# EX-YU_16K_C64_CART.net
KiCad netlist of a schematic drawn in EAGLE
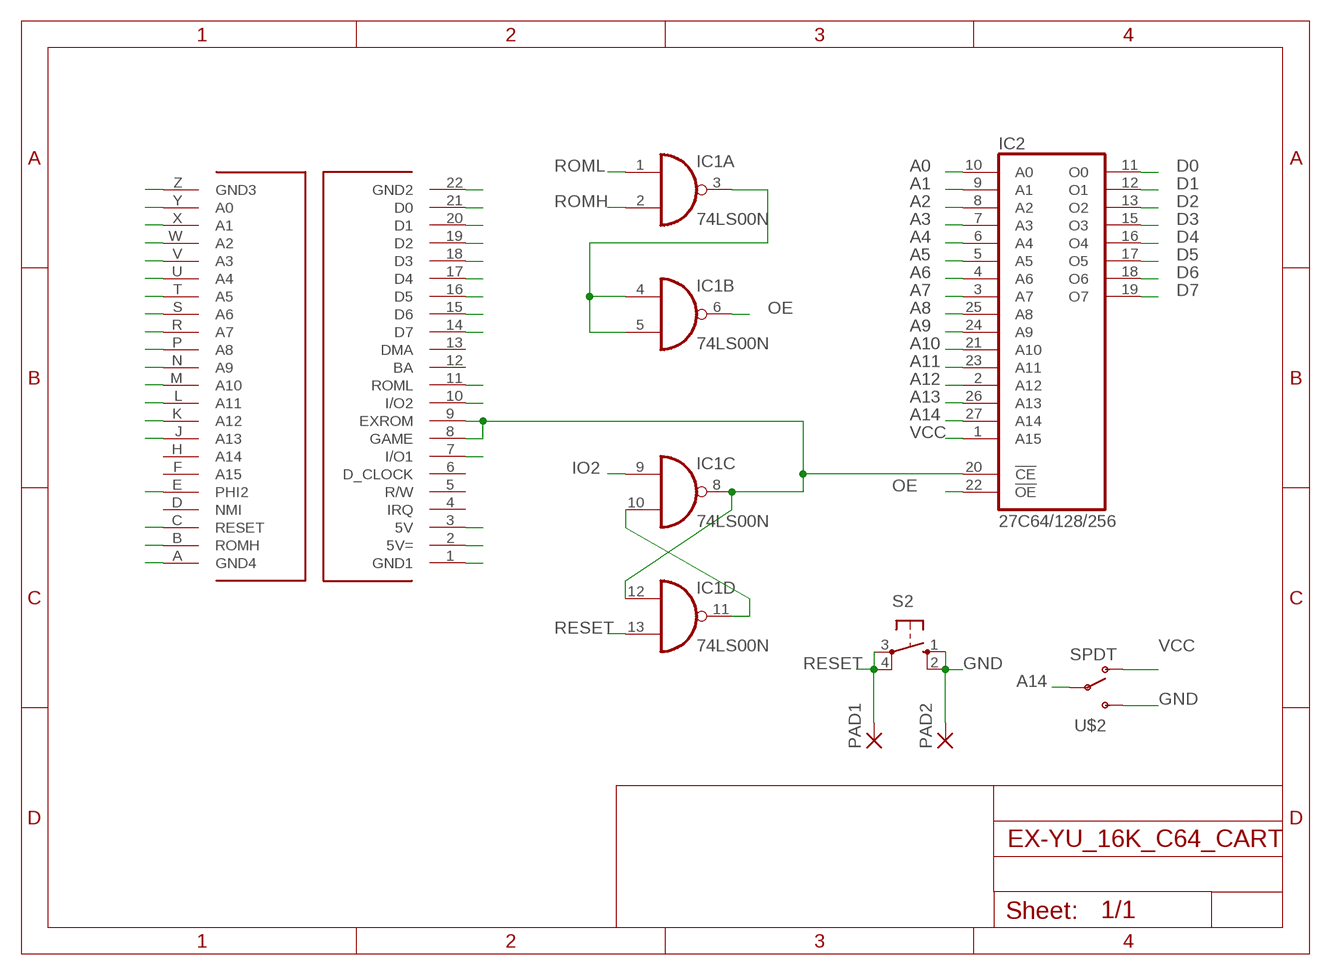
[diagram p0: schematic, sheet 1]

(export (version "E")
  (design (tool "Eeschema 10.0.6"))
  (components
    (comp (ref "IC1")
      (value "74LS00N")
      (footprint "eagle-import:DIL14")
      (libsource (lib "eagle-import") (part "7400NLS"))
    )
    (comp (ref "IC2")
      (value "27C64/128/256")
      (footprint "eagle-import:DIL28")
      (libsource (lib "eagle-import") (part "27512"))
    )
    (comp (ref "PAD1")
      (value "SMD5")
      (footprint "eagle-import:SMD2,54-5,08")
      (libsource (lib "eagle-import") (part "SMD5"))
    )
    (comp (ref "PAD2")
      (value "SMD5")
      (footprint "eagle-import:SMD2,54-5,08")
      (libsource (lib "eagle-import") (part "SMD5"))
    )
    (comp (ref "S2")
      (value "10-XX")
      (footprint "eagle-import:B3F-10XX")
      (fields (field (name "MPN") "B3F-1000"))
      (libsource (lib "eagle-import") (part "10-XX"))
    )
    (comp (ref "U$1")
      (value "C64_EXPANSION__CARTRIDGE")
      (footprint "eagle-import:C64_EXPANSION__CARTRIDGE")
      (libsource (lib "eagle-import") (part "C64_EXPANSION__CARTRIDGE"))
    )
    (comp (ref "U$2")
      (value "SPDT")
      (footprint "eagle-import:SPDT-SLIDE")
      (libsource (lib "eagle-import") (part "SPDT"))
    )
  )
  (nets
    (net (code "1") (name "/A0") (class "Default")
      (node (ref "IC2") (pin "10") (pinfunction "A0_10") (pintype "input"))
      (node (ref "U$1") (pin "Y") (pinfunction "A0_Y") (pintype "bidirectional"))
    )
    (net (code "2") (name "/A1") (class "Default")
      (node (ref "IC2") (pin "9") (pinfunction "A1_9") (pintype "input"))
      (node (ref "U$1") (pin "X") (pinfunction "A1_X") (pintype "bidirectional"))
    )
    (net (code "3") (name "/A2") (class "Default")
      (node (ref "IC2") (pin "8") (pinfunction "A2_8") (pintype "input"))
      (node (ref "U$1") (pin "W") (pinfunction "A2_W") (pintype "bidirectional"))
    )
    (net (code "4") (name "/A3") (class "Default")
      (node (ref "IC2") (pin "7") (pinfunction "A3_7") (pintype "input"))
      (node (ref "U$1") (pin "V") (pinfunction "A3_V") (pintype "bidirectional"))
    )
    (net (code "5") (name "/A4") (class "Default")
      (node (ref "IC2") (pin "6") (pinfunction "A4_6") (pintype "input"))
      (node (ref "U$1") (pin "U") (pinfunction "A4_U") (pintype "bidirectional"))
    )
    (net (code "6") (name "/A5") (class "Default")
      (node (ref "IC2") (pin "5") (pinfunction "A5_5") (pintype "input"))
      (node (ref "U$1") (pin "T") (pinfunction "A5_T") (pintype "bidirectional"))
    )
    (net (code "7") (name "/A6") (class "Default")
      (node (ref "IC2") (pin "4") (pinfunction "A6_4") (pintype "input"))
      (node (ref "U$1") (pin "S") (pinfunction "A6_S") (pintype "bidirectional"))
    )
    (net (code "8") (name "/A7") (class "Default")
      (node (ref "IC2") (pin "3") (pinfunction "A7_3") (pintype "input"))
      (node (ref "U$1") (pin "R") (pinfunction "A7_R") (pintype "bidirectional"))
    )
    (net (code "9") (name "/A8") (class "Default")
      (node (ref "IC2") (pin "25") (pinfunction "A8_25") (pintype "input"))
      (node (ref "U$1") (pin "P") (pinfunction "A8_P") (pintype "bidirectional"))
    )
    (net (code "10") (name "/A9") (class "Default")
      (node (ref "IC2") (pin "24") (pinfunction "A9_24") (pintype "input"))
      (node (ref "U$1") (pin "N") (pinfunction "A9_N") (pintype "bidirectional"))
    )
    (net (code "11") (name "/A10") (class "Default")
      (node (ref "IC2") (pin "21") (pinfunction "A10_21") (pintype "input"))
      (node (ref "U$1") (pin "M") (pinfunction "A10_M") (pintype "bidirectional"))
    )
    (net (code "12") (name "/A11") (class "Default")
      (node (ref "IC2") (pin "23") (pinfunction "A11_23") (pintype "input"))
      (node (ref "U$1") (pin "L") (pinfunction "A11_L") (pintype "bidirectional"))
    )
    (net (code "13") (name "/A12") (class "Default")
      (node (ref "IC2") (pin "2") (pinfunction "A12_2") (pintype "input"))
      (node (ref "U$1") (pin "K") (pinfunction "A12_K") (pintype "bidirectional"))
    )
    (net (code "14") (name "/A13") (class "Default")
      (node (ref "IC2") (pin "26") (pinfunction "A13_26") (pintype "input"))
      (node (ref "U$1") (pin "J") (pinfunction "A13_J") (pintype "bidirectional"))
    )
    (net (code "15") (name "/A14") (class "Default")
      (node (ref "IC2") (pin "27") (pinfunction "A14_27") (pintype "input"))
      (node (ref "U$2") (pin "2") (pinfunction "2_2") (pintype "passive"))
    )
    (net (code "16") (name "/D0") (class "Default")
      (node (ref "IC2") (pin "11") (pinfunction "O0_11") (pintype "tri_state"))
      (node (ref "U$1") (pin "21") (pinfunction "D0_21") (pintype "bidirectional"))
    )
    (net (code "17") (name "/D1") (class "Default")
      (node (ref "IC2") (pin "12") (pinfunction "O1_12") (pintype "tri_state"))
      (node (ref "U$1") (pin "20") (pinfunction "D1_20") (pintype "bidirectional"))
    )
    (net (code "18") (name "/D2") (class "Default")
      (node (ref "IC2") (pin "13") (pinfunction "O2_13") (pintype "tri_state"))
      (node (ref "U$1") (pin "19") (pinfunction "D2_19") (pintype "bidirectional"))
    )
    (net (code "19") (name "/D3") (class "Default")
      (node (ref "IC2") (pin "15") (pinfunction "O3_15") (pintype "tri_state"))
      (node (ref "U$1") (pin "18") (pinfunction "D3_18") (pintype "bidirectional"))
    )
    (net (code "20") (name "/D4") (class "Default")
      (node (ref "IC2") (pin "16") (pinfunction "O4_16") (pintype "tri_state"))
      (node (ref "U$1") (pin "17") (pinfunction "D4_17") (pintype "bidirectional"))
    )
    (net (code "21") (name "/D5") (class "Default")
      (node (ref "IC2") (pin "17") (pinfunction "O5_17") (pintype "tri_state"))
      (node (ref "U$1") (pin "16") (pinfunction "D5_16") (pintype "bidirectional"))
    )
    (net (code "22") (name "/D6") (class "Default")
      (node (ref "IC2") (pin "18") (pinfunction "O6_18") (pintype "tri_state"))
      (node (ref "U$1") (pin "15") (pinfunction "D6_15") (pintype "bidirectional"))
    )
    (net (code "23") (name "/D7") (class "Default")
      (node (ref "IC2") (pin "19") (pinfunction "O7_19") (pintype "tri_state"))
      (node (ref "U$1") (pin "14") (pinfunction "D7_14") (pintype "bidirectional"))
    )
    (net (code "24") (name "/GND") (class "Default")
      (node (ref "PAD2") (pin "1") (pinfunction "P_1") (pintype "passive"))
      (node (ref "S2") (pin "1") (pinfunction "S_1") (pintype "passive"))
      (node (ref "S2") (pin "2") (pinfunction "S1_2") (pintype "passive"))
      (node (ref "U$1") (pin "1") (pinfunction "GND1_1") (pintype "bidirectional"))
      (node (ref "U$1") (pin "22") (pinfunction "GND2_22") (pintype "bidirectional"))
      (node (ref "U$1") (pin "A") (pinfunction "GND4_A") (pintype "bidirectional"))
      (node (ref "U$1") (pin "Z") (pinfunction "GND3_Z") (pintype "bidirectional"))
      (node (ref "U$2") (pin "3") (pinfunction "3_3") (pintype "passive"))
    )
    (net (code "25") (name "/IO2") (class "Default")
      (node (ref "IC1") (pin "9") (pinfunction "I0_9") (pintype "input"))
      (node (ref "U$1") (pin "10") (pinfunction "I/O2_10") (pintype "bidirectional"))
    )
    (net (code "26") (name "/OE") (class "Default")
      (node (ref "IC1") (pin "6") (pinfunction "O_6") (pintype "output"))
      (node (ref "IC2") (pin "22") (pinfunction "~{OE}_22") (pintype "input"))
    )
    (net (code "27") (name "/RESET") (class "Default")
      (node (ref "IC1") (pin "13") (pinfunction "I1_13") (pintype "input"))
      (node (ref "PAD1") (pin "1") (pinfunction "P_1") (pintype "passive"))
      (node (ref "S2") (pin "3") (pinfunction "P_3") (pintype "passive"))
      (node (ref "S2") (pin "4") (pinfunction "P1_4") (pintype "passive"))
      (node (ref "U$1") (pin "C") (pinfunction "RESET_C") (pintype "bidirectional"))
    )
    (net (code "28") (name "/ROMH") (class "Default")
      (node (ref "IC1") (pin "2") (pinfunction "I1_2") (pintype "input"))
      (node (ref "U$1") (pin "B") (pinfunction "ROMH_B") (pintype "bidirectional"))
    )
    (net (code "29") (name "/ROML") (class "Default")
      (node (ref "IC1") (pin "1") (pinfunction "I0_1") (pintype "input"))
      (node (ref "U$1") (pin "11") (pinfunction "ROML_11") (pintype "bidirectional"))
    )
    (net (code "30") (name "/VCC") (class "Default")
      (node (ref "IC2") (pin "1") (pinfunction "A15_1") (pintype "input"))
      (node (ref "U$1") (pin "2") (pinfunction "5V=_2") (pintype "bidirectional"))
      (node (ref "U$1") (pin "3") (pinfunction "5V_3") (pintype "bidirectional"))
      (node (ref "U$2") (pin "1") (pinfunction "1_1") (pintype "passive"))
    )
    (net (code "31") (name "Net-(IC1A-O)") (class "Default")
      (node (ref "IC1") (pin "3") (pinfunction "O_3") (pintype "output"))
      (node (ref "IC1") (pin "4") (pinfunction "I0_4") (pintype "input"))
      (node (ref "IC1") (pin "5") (pinfunction "I1_5") (pintype "input"))
    )
    (net (code "32") (name "Net-(IC1C-I1)") (class "Default")
      (node (ref "IC1") (pin "10") (pinfunction "I1_10") (pintype "input"))
      (node (ref "IC1") (pin "11") (pinfunction "O_11") (pintype "output"))
    )
    (net (code "33") (name "Net-(IC1C-O)") (class "Default")
      (node (ref "IC1") (pin "12") (pinfunction "I0_12") (pintype "input"))
      (node (ref "IC1") (pin "8") (pinfunction "O_8") (pintype "output"))
      (node (ref "IC2") (pin "20") (pinfunction "~{CE}_20") (pintype "input"))
      (node (ref "U$1") (pin "8") (pinfunction "GAME_8") (pintype "bidirectional"))
      (node (ref "U$1") (pin "9") (pinfunction "EXROM_9") (pintype "bidirectional"))
    )
    (net (code "34") (name "unconnected-(U$1-A14-PadH)") (class "Default")
      (node (ref "U$1") (pin "H") (pinfunction "A14_H") (pintype "bidirectional"))
    )
    (net (code "35") (name "unconnected-(U$1-A15-PadF)") (class "Default")
      (node (ref "U$1") (pin "F") (pinfunction "A15_F") (pintype "bidirectional"))
    )
    (net (code "36") (name "unconnected-(U$1-BA-Pad12)") (class "Default")
      (node (ref "U$1") (pin "12") (pinfunction "BA_12") (pintype "bidirectional"))
    )
    (net (code "37") (name "unconnected-(U$1-DMA-Pad13)") (class "Default")
      (node (ref "U$1") (pin "13") (pinfunction "DMA_13") (pintype "bidirectional"))
    )
    (net (code "38") (name "unconnected-(U$1-D_CLOCK-Pad6)") (class "Default")
      (node (ref "U$1") (pin "6") (pinfunction "D_CLOCK_6") (pintype "bidirectional"))
    )
    (net (code "39") (name "unconnected-(U$1-IRQ-Pad4)") (class "Default")
      (node (ref "U$1") (pin "4") (pinfunction "IRQ_4") (pintype "bidirectional"))
    )
    (net (code "40") (name "unconnected-(U$1-I{slash}O1-Pad7)") (class "Default")
      (node (ref "U$1") (pin "7") (pinfunction "I/O1_7") (pintype "bidirectional"))
    )
    (net (code "41") (name "unconnected-(U$1-NMI-PadD)") (class "Default")
      (node (ref "U$1") (pin "D") (pinfunction "NMI_D") (pintype "bidirectional"))
    )
    (net (code "42") (name "unconnected-(U$1-PHI2-PadE)") (class "Default")
      (node (ref "U$1") (pin "E") (pinfunction "PHI2_E") (pintype "bidirectional"))
    )
    (net (code "43") (name "unconnected-(U$1-R{slash}W-Pad5)") (class "Default")
      (node (ref "U$1") (pin "5") (pinfunction "R/W_5") (pintype "bidirectional"))
    )
  )
)
